# Callisto_Teknic_MSO_PBx4_single.net
KiCad netlist of a schematic drawn in EAGLE
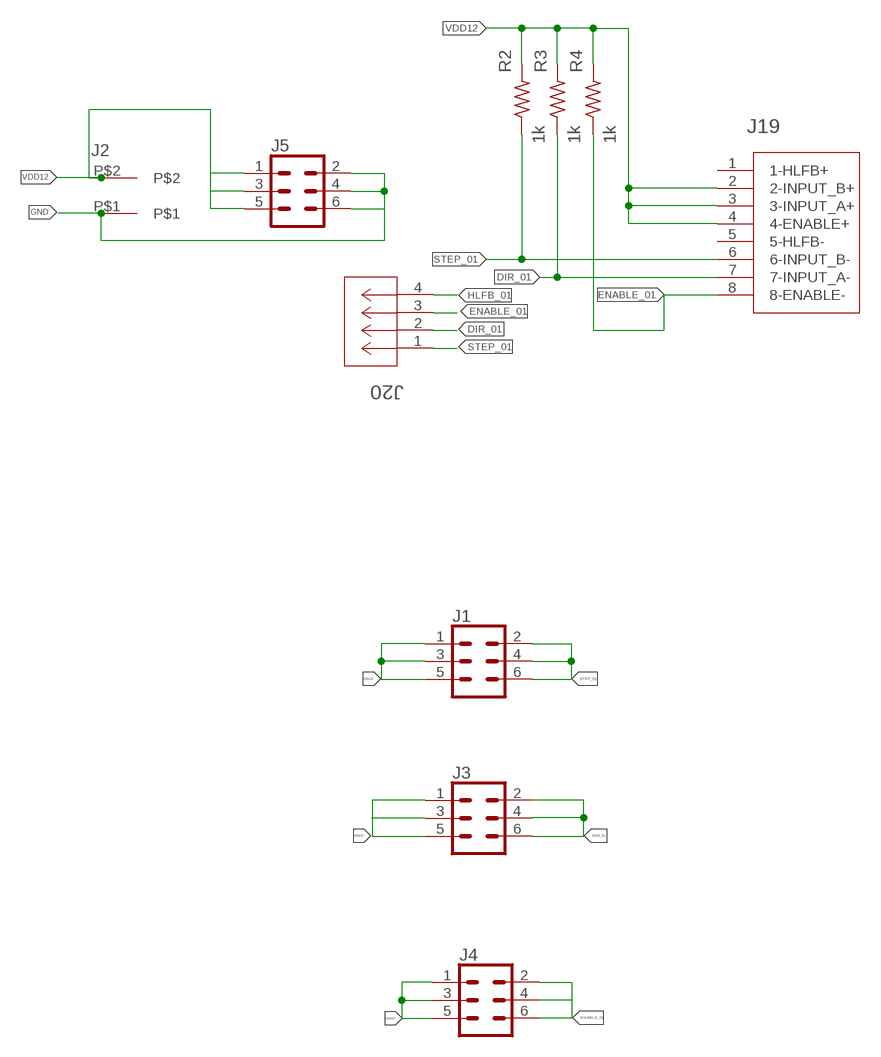
[diagram p0: schematic, sheet 1]

(export (version "E")
  (design (tool "Eeschema 10.0.6"))
  (components
    (comp (ref "J1")
      (value "CONN_03X2")
      (footprint "eagle-import:2X3")
      (libsource (lib "eagle-import") (part "CONN_03X2"))
    )
    (comp (ref "J2")
      (value "2-pos")
      (footprint "eagle-import:2_3.81MM_PITCH")
      (fields (field (name "PARTNO") "691322310002"))
      (libsource (lib "eagle-import") (part "3.81MM_1_X_2_RT_ANGLE_PLUG_HEADER"))
    )
    (comp (ref "J3")
      (value "CONN_03X2")
      (footprint "eagle-import:2X3")
      (libsource (lib "eagle-import") (part "CONN_03X2"))
    )
    (comp (ref "J4")
      (value "CONN_03X2")
      (footprint "eagle-import:2X3")
      (libsource (lib "eagle-import") (part "CONN_03X2"))
    )
    (comp (ref "J5")
      (value "CONN_03X2")
      (footprint "eagle-import:2X3")
      (libsource (lib "eagle-import") (part "CONN_03X2"))
    )
    (comp (ref "J19")
      (value "TEKNIC_8PIN_MOTOR")
      (footprint "eagle-import:CON_39281083")
      (fields
        (field (name "MANUFACTURER_PART_NUMBER") "39281083")
        (field (name "COPYRIGHT") "Copyright (C) 2022 Ultra Librarian. All rights reserved.")
      )
      (libsource (lib "eagle-import") (part "TEKNIC_8PIN_MOTOR"))
    )
    (comp (ref "J20")
      (value "CONN_530470410_PICOBLADE_X_4")
      (footprint "eagle-import:CON_530470410_MOL")
      (fields
        (field (name "MANUFACTURER_PART_NUMBER") "530470410")
        (field (name "COPYRIGHT") "Copyright (C) 2022 Ultra Librarian. All rights reserved.")
      )
      (libsource (lib "eagle-import") (part "CONN_530470410_PICOBLADE_X_4"))
    )
    (comp (ref "R2")
      (value "1k")
      (footprint "eagle-import:0805")
      (libsource (lib "eagle-import") (part "R_0805"))
    )
    (comp (ref "R3")
      (value "1k")
      (footprint "eagle-import:0805")
      (libsource (lib "eagle-import") (part "R_0805"))
    )
    (comp (ref "R4")
      (value "1k")
      (footprint "eagle-import:0805")
      (libsource (lib "eagle-import") (part "R_0805"))
    )
  )
  (nets
    (net (code "1") (name "DIR_01") (class "Default")
      (node (ref "J19") (pin "7") (pinfunction "7-INPUT_A-_7") (pintype "passive"))
      (node (ref "J20") (pin "2") (pinfunction "2_2") (pintype "passive"))
      (node (ref "J3") (pin "2") (pinfunction "2_2") (pintype "passive"))
      (node (ref "J3") (pin "4") (pinfunction "4_4") (pintype "passive"))
      (node (ref "J3") (pin "6") (pinfunction "6_6") (pintype "passive"))
      (node (ref "R3") (pin "1") (pinfunction "1_1") (pintype "passive"))
    )
    (net (code "2") (name "ENABLE_01") (class "Default")
      (node (ref "J19") (pin "8") (pinfunction "8-ENABLE-_8") (pintype "passive"))
      (node (ref "J20") (pin "3") (pinfunction "3_3") (pintype "passive"))
      (node (ref "J4") (pin "2") (pinfunction "2_2") (pintype "passive"))
      (node (ref "J4") (pin "4") (pinfunction "4_4") (pintype "passive"))
      (node (ref "J4") (pin "6") (pinfunction "6_6") (pintype "passive"))
      (node (ref "R4") (pin "1") (pinfunction "1_1") (pintype "passive"))
    )
    (net (code "3") (name "GND") (class "Default")
      (node (ref "J1") (pin "1") (pinfunction "1_1") (pintype "passive"))
      (node (ref "J1") (pin "3") (pinfunction "3_3") (pintype "passive"))
      (node (ref "J1") (pin "5") (pinfunction "5_5") (pintype "passive"))
      (node (ref "J2") (pin "P$1") (pinfunction "P$1_P$1") (pintype "bidirectional"))
      (node (ref "J3") (pin "1") (pinfunction "1_1") (pintype "passive"))
      (node (ref "J3") (pin "3") (pinfunction "3_3") (pintype "passive"))
      (node (ref "J3") (pin "5") (pinfunction "5_5") (pintype "passive"))
      (node (ref "J4") (pin "1") (pinfunction "1_1") (pintype "passive"))
      (node (ref "J4") (pin "3") (pinfunction "3_3") (pintype "passive"))
      (node (ref "J4") (pin "5") (pinfunction "5_5") (pintype "passive"))
      (node (ref "J5") (pin "2") (pinfunction "2_2") (pintype "passive"))
      (node (ref "J5") (pin "4") (pinfunction "4_4") (pintype "passive"))
      (node (ref "J5") (pin "6") (pinfunction "6_6") (pintype "passive"))
    )
    (net (code "4") (name "HLFB_01") (class "Default")
      (node (ref "J20") (pin "4") (pinfunction "4_4") (pintype "passive"))
    )
    (net (code "5") (name "STEP_01") (class "Default")
      (node (ref "J1") (pin "2") (pinfunction "2_2") (pintype "passive"))
      (node (ref "J1") (pin "4") (pinfunction "4_4") (pintype "passive"))
      (node (ref "J1") (pin "6") (pinfunction "6_6") (pintype "passive"))
      (node (ref "J19") (pin "6") (pinfunction "6-INPUT_B-_6") (pintype "passive"))
      (node (ref "J20") (pin "1") (pinfunction "1_1") (pintype "passive"))
      (node (ref "R2") (pin "1") (pinfunction "1_1") (pintype "passive"))
    )
    (net (code "6") (name "VDD12") (class "Default")
      (node (ref "J19") (pin "2") (pinfunction "2-INPUT_B+_2") (pintype "passive"))
      (node (ref "J19") (pin "3") (pinfunction "3-INPUT_A+_3") (pintype "passive"))
      (node (ref "J19") (pin "4") (pinfunction "4-ENABLE+_4") (pintype "passive"))
      (node (ref "J2") (pin "P$2") (pinfunction "P$2_P$2") (pintype "bidirectional"))
      (node (ref "J5") (pin "1") (pinfunction "1_1") (pintype "passive"))
      (node (ref "J5") (pin "3") (pinfunction "3_3") (pintype "passive"))
      (node (ref "J5") (pin "5") (pinfunction "5_5") (pintype "passive"))
      (node (ref "R2") (pin "2") (pinfunction "2_2") (pintype "passive"))
      (node (ref "R3") (pin "2") (pinfunction "2_2") (pintype "passive"))
      (node (ref "R4") (pin "2") (pinfunction "2_2") (pintype "passive"))
    )
    (net (code "7") (name "unconnected-(J19-1-HLFB+-Pad1)") (class "Default")
      (node (ref "J19") (pin "1") (pinfunction "1-HLFB+_1") (pintype "passive"))
    )
    (net (code "8") (name "unconnected-(J19-5-HLFB--Pad5)") (class "Default")
      (node (ref "J19") (pin "5") (pinfunction "5-HLFB-_5") (pintype "passive"))
    )
  )
)
